# Diode_Model.net
KiCad netlist of a schematic drawn in Altium Designer
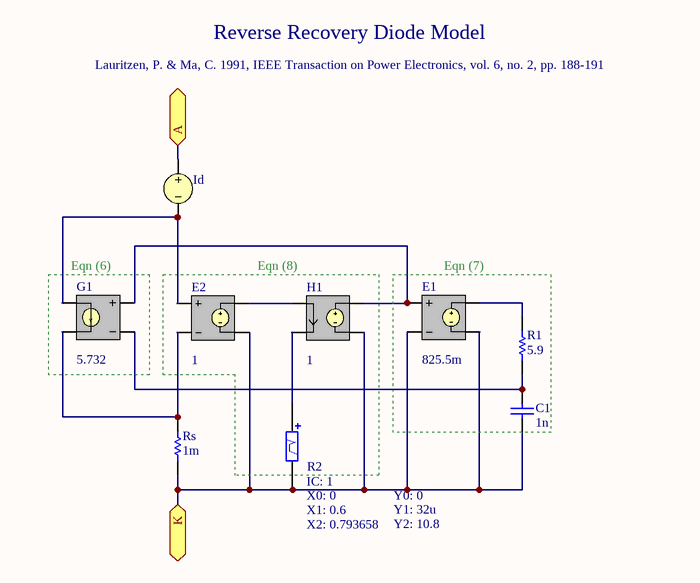
[diagram p0: Diode Model.SchDoc]

(export (version "E")
  (design (tool "Eeschema 10.0.6"))
  (components
    (comp (ref "C1")
      (value "1n")
      (footprint "RAD-0.3")
      (description "Capacitor")
      (fields (field (name "Comment") "Cap") (field (name "PUBLISHER") "Altium Limited"))
      (libsource (lib "Miscellaneous Devices") (part "Cap"))
    )
    (comp (ref "E1")
      (value "825.5m")
      (description "Voltage Controlled Voltage Source")
      (fields (field (name "GAIN") "825.5m") (field (name "PUBLISHER") "Altium Limited"))
      (libsource (lib "Simulation Sources") (part "ESRC"))
    )
    (comp (ref "E2")
      (value "1")
      (description "Voltage Controlled Voltage Source")
      (fields (field (name "GAIN") "1") (field (name "PUBLISHER") "Altium Limited"))
      (libsource (lib "Simulation Sources") (part "ESRC"))
    )
    (comp (ref "G1")
      (value "5.732")
      (description "Voltage Controlled Current Source")
      (fields (field (name "GAIN") "5.732") (field (name "PUBLISHER") "Altium Limited"))
      (libsource (lib "Simulation Sources") (part "GSRC"))
    )
    (comp (ref "H1")
      (value "1")
      (description "Current Controlled Voltage Source")
      (fields (field (name "GAIN") "1") (field (name "PUBLISHER") "Altium Limited"))
      (libsource (lib "Simulation Sources") (part "HSRC"))
    )
    (comp (ref "Id")
      (value "VSRC")
      (description "Voltage Source")
      (fields (field (name "PUBLISHER") "Altium Limited"))
      (libsource (lib "Simulation Sources") (part "VSRC"))
    )
    (comp (ref "R1")
      (value "5.9")
      (footprint "AXIAL-0.3")
      (description "Resistor")
      (fields (field (name "Comment") "Res1") (field (name "PUBLISHER") "Altium Limited"))
      (libsource (lib "Miscellaneous Devices") (part "Res1"))
    )
    (comp (ref "R2")
      (value "SIMPLIS VPWLR2")
      (description "Voltage-Controlled Piecewise Linear Resistor (2-segment)")
      (fields
        (field (name "IC") "1")
        (field (name "X0") "0")
        (field (name "Y0") "0")
        (field (name "X1") "0.6")
        (field (name "Y1") "32u")
        (field (name "X2") "0.793658")
        (field (name "Y2") "10.8")
        (field (name "PUBLISHER") "Altium Limited")
      )
      (libsource (lib "SIMPLIS Devices") (part "SIMPLIS VPWLR2"))
    )
    (comp (ref "Rs")
      (value "1m")
      (footprint "AXIAL-0.3")
      (description "Resistor")
      (fields (field (name "Comment") "Res1") (field (name "PUBLISHER") "Altium Limited"))
      (libsource (lib "Miscellaneous Devices") (part "Res1"))
    )
  )
  (nets
    (net (code "1") (name "/A") (class "Default")
      (node (ref "Id") (pin "1") (pinfunction "1_1") (pintype "passive"))
    )
    (net (code "2") (name "/K") (class "Default")
      (node (ref "C1") (pin "1") (pinfunction "1_1") (pintype "passive"))
      (node (ref "E1") (pin "2") (pinfunction "NC-_2") (pintype "passive"))
      (node (ref "E1") (pin "4") (pinfunction "N-_4") (pintype "passive"))
      (node (ref "E2") (pin "4") (pinfunction "N-_4") (pintype "passive"))
      (node (ref "H1") (pin "4") (pinfunction "N-_4") (pintype "passive"))
      (node (ref "R2") (pin "2") (pinfunction "2_2") (pintype "passive"))
      (node (ref "Rs") (pin "1") (pinfunction "1_1") (pintype "passive"))
    )
    (net (code "3") (name "Net-(E1-N+)") (class "Default")
      (node (ref "E1") (pin "3") (pinfunction "N+_3") (pintype "passive"))
      (node (ref "R1") (pin "2") (pinfunction "2_2") (pintype "passive"))
    )
    (net (code "4") (name "Net-(E1-NC+)") (class "Default")
      (node (ref "E1") (pin "1") (pinfunction "NC+_1") (pintype "passive"))
      (node (ref "G1") (pin "1") (pinfunction "NC+_1") (pintype "passive"))
      (node (ref "H1") (pin "3") (pinfunction "N+_3") (pintype "passive"))
    )
    (net (code "5") (name "Net-(E2-N+)") (class "Default")
      (node (ref "E2") (pin "3") (pinfunction "N+_3") (pintype "passive"))
      (node (ref "H1") (pin "1") (pinfunction "NC+_1") (pintype "passive"))
    )
    (net (code "6") (name "Net-(E2-NC+)") (class "Default")
      (node (ref "E2") (pin "1") (pinfunction "NC+_1") (pintype "passive"))
      (node (ref "G1") (pin "3") (pinfunction "N+_3") (pintype "passive"))
      (node (ref "Id") (pin "2") (pinfunction "2_2") (pintype "passive"))
    )
    (net (code "7") (name "Net-(E2-NC-)") (class "Default")
      (node (ref "E2") (pin "2") (pinfunction "NC-_2") (pintype "passive"))
      (node (ref "G1") (pin "4") (pinfunction "N-_4") (pintype "passive"))
      (node (ref "Rs") (pin "2") (pinfunction "2_2") (pintype "passive"))
    )
    (net (code "8") (name "Net-(G1-NC-)") (class "Default")
      (node (ref "C1") (pin "2") (pinfunction "2_2") (pintype "passive"))
      (node (ref "G1") (pin "2") (pinfunction "NC-_2") (pintype "passive"))
      (node (ref "R1") (pin "1") (pinfunction "1_1") (pintype "passive"))
    )
    (net (code "9") (name "Net-(H1-NC-)") (class "Default")
      (node (ref "H1") (pin "2") (pinfunction "NC-_2") (pintype "passive"))
      (node (ref "R2") (pin "1") (pinfunction "1_1") (pintype "passive"))
    )
  )
)
